# AWG_mechanics.net
KiCad netlist of a schematic drawn in Altium Designer
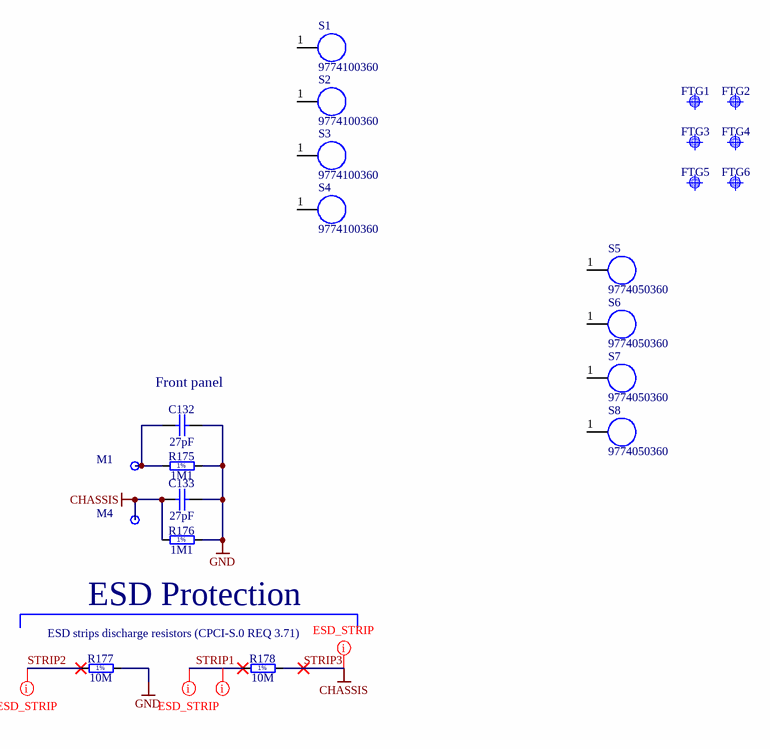
[diagram p0: AWG_mechanics.SchDoc]

(export (version "E")
  (design (tool "Eeschema 10.0.6"))
  (components
    (comp (ref "C132")
      (value "27pF")
      (footprint "CAPC1005X55N")
      (description "Non-polarised capacitor")
      (fields
        (field (name "PART NUMBER") "CC0402_27PF_50V_5%_C0G")
        (field (name "VOLTAGE") "50V")
        (field (name "AUTHOR") "CERN DEM JLC")
      )
      (libsource (lib "Capacitors") (part "Capacitor - non polarized"))
    )
    (comp (ref "C133")
      (value "27pF")
      (footprint "CAPC1005X55N")
      (description "Non-polarised capacitor")
      (fields
        (field (name "PART NUMBER") "CC0402_27PF_50V_5%_C0G")
        (field (name "VOLTAGE") "50V")
        (field (name "AUTHOR") "CERN DEM JLC")
      )
      (libsource (lib "Capacitors") (part "Capacitor - non polarized"))
    )
    (comp (ref "FTG1")
      (value "Use only in PCB")
      (footprint "FIDUCIAL_TOP_C100-200")
      (description "Fiducial Target")
      (fields (field (name "PART NUMBER") "FIDUCIAL_TARGET_C100-200") (field (name "AUTHOR") "CERN DEM JLC"))
      (libsource (lib "Eletro-mechanical") (part "Fiducial Target"))
    )
    (comp (ref "FTG2")
      (value "Use only in PCB")
      (footprint "FIDUCIAL_TOP_S100-200")
      (description "Fiducial Target")
      (fields (field (name "PART NUMBER") "FIDUCIAL_TARGET_S100-200") (field (name "AUTHOR") "CERN DEM JLC"))
      (libsource (lib "Eletro-mechanical") (part "Fiducial Target"))
    )
    (comp (ref "FTG3")
      (value "Use only in PCB")
      (footprint "FIDUCIAL_TOP_C100-200")
      (description "Fiducial Target")
      (fields (field (name "PART NUMBER") "FIDUCIAL_TARGET_C100-200") (field (name "AUTHOR") "CERN DEM JLC"))
      (libsource (lib "Eletro-mechanical") (part "Fiducial Target"))
    )
    (comp (ref "FTG4")
      (value "Use only in PCB")
      (footprint "FIDUCIAL_TOP_S100-200")
      (description "Fiducial Target")
      (fields (field (name "PART NUMBER") "FIDUCIAL_TARGET_S100-200") (field (name "AUTHOR") "CERN DEM JLC"))
      (libsource (lib "Eletro-mechanical") (part "Fiducial Target"))
    )
    (comp (ref "FTG5")
      (value "Use only in PCB")
      (footprint "FIDUCIAL_TOP_C100-200")
      (description "Fiducial Target")
      (fields (field (name "PART NUMBER") "FIDUCIAL_TARGET_C100-200") (field (name "AUTHOR") "CERN DEM JLC"))
      (libsource (lib "Eletro-mechanical") (part "Fiducial Target"))
    )
    (comp (ref "FTG6")
      (value "Use only in PCB")
      (footprint "FIDUCIAL_TOP_S100-200")
      (description "Fiducial Target")
      (fields (field (name "PART NUMBER") "FIDUCIAL_TARGET_S100-200") (field (name "AUTHOR") "CERN DEM JLC"))
      (libsource (lib "Eletro-mechanical") (part "Fiducial Target"))
    )
    (comp (ref "M1")
      (value "Plated Hole")
      (footprint "MTG300_600")
      (description "Single Terminal Socket")
      (fields (field (name "PART NUMBER") "PLATED_HOLE3.0_PAD6.0") (field (name "AUTHOR") "CERN DEM JLC"))
      (libsource (lib "Eletro-mechanical") (part "Single Terminal Socket"))
    )
    (comp (ref "M4")
      (value "Plated Hole")
      (footprint "MTG300_600")
      (description "Single Terminal Socket")
      (fields (field (name "PART NUMBER") "PLATED_HOLE3.0_PAD6.0") (field (name "AUTHOR") "CERN DEM JLC"))
      (libsource (lib "Eletro-mechanical") (part "Single Terminal Socket"))
    )
    (comp (ref "R175")
      (value "1M1")
      (footprint "RESC2012X60N")
      (description "Resistor - 1%")
      (fields
        (field (name "PART NUMBER") "R0805_1M1_1%_0.125W_100PPM")
        (field (name "POWER") "0.125W")
        (field (name "AUTHOR") "CERN DEM JLC")
      )
      (libsource (lib "Resistors") (part "Resistor - 1%"))
    )
    (comp (ref "R176")
      (value "1M1")
      (footprint "RESC2012X60N")
      (description "Resistor - 1%")
      (fields
        (field (name "PART NUMBER") "R0805_1M1_1%_0.125W_100PPM")
        (field (name "POWER") "0.125W")
        (field (name "AUTHOR") "CERN DEM JLC")
      )
      (libsource (lib "Resistors") (part "Resistor - 1%"))
    )
    (comp (ref "R177")
      (value "10M")
      (footprint "RESC2113X55N")
      (description "Resistor - 1%")
      (fields
        (field (name "PART NUMBER") "R0805_10M_1%_0.125W_100PPM_VISHAY_CRCW e3")
        (field (name "POWER") "0.125W")
        (field (name "AUTHOR") "CERN DEM BC")
      )
      (libsource (lib "Resistors") (part "Resistor - 1%"))
    )
    (comp (ref "R178")
      (value "10M")
      (footprint "RESC2113X55N")
      (description "Resistor - 1%")
      (fields
        (field (name "PART NUMBER") "R0805_10M_1%_0.125W_100PPM_VISHAY_CRCW e3")
        (field (name "POWER") "0.125W")
        (field (name "AUTHOR") "CERN DEM BC")
      )
      (libsource (lib "Resistors") (part "Resistor - 1%"))
    )
    (comp (ref "S1")
      (value "9774100360")
      (footprint "9774100360")
      (description "WA-SMSI SMD Steel Spacer with internal Thread")
      (fields (field (name "MANUFACTURER") "Wurth Elektronik") (field (name "CREATED BY") "Baojun Chen"))
      (libsource (lib "Altium_SMSI_SMT_STEEL_SPACER_M2_5_THREAD_INTERNAL_rev15a") (part "WA-SMSI,  9774100360"))
    )
    (comp (ref "S2")
      (value "9774100360")
      (footprint "9774100360")
      (description "WA-SMSI SMD Steel Spacer with internal Thread")
      (fields (field (name "MANUFACTURER") "Wurth Elektronik") (field (name "CREATED BY") "Baojun Chen"))
      (libsource (lib "Altium_SMSI_SMT_STEEL_SPACER_M2_5_THREAD_INTERNAL_rev15a") (part "WA-SMSI,  9774100360"))
    )
    (comp (ref "S3")
      (value "9774100360")
      (footprint "9774100360")
      (description "WA-SMSI SMD Steel Spacer with internal Thread")
      (fields (field (name "MANUFACTURER") "Wurth Elektronik") (field (name "CREATED BY") "Baojun Chen"))
      (libsource (lib "Altium_SMSI_SMT_STEEL_SPACER_M2_5_THREAD_INTERNAL_rev15a") (part "WA-SMSI,  9774100360"))
    )
    (comp (ref "S4")
      (value "9774100360")
      (footprint "9774100360")
      (description "WA-SMSI SMD Steel Spacer with internal Thread")
      (fields (field (name "MANUFACTURER") "Wurth Elektronik") (field (name "CREATED BY") "Baojun Chen"))
      (libsource (lib "Altium_SMSI_SMT_STEEL_SPACER_M2_5_THREAD_INTERNAL_rev15a") (part "WA-SMSI,  9774100360"))
    )
    (comp (ref "S5")
      (value "9774050360")
      (footprint "9774050360")
      (description "WA-SMSI SMD Steel Spacer with internal Thread")
      (fields (field (name "MANUFACTURER") "Wurth Elektronik") (field (name "CREATED BY") "Baojun Chen"))
      (libsource (lib "Altium_SMSI_SMT_STEEL_SPACER_M2_5_THREAD_INTERNAL_rev15a") (part "WA-SMSI,  9774050360"))
    )
    (comp (ref "S6")
      (value "9774050360")
      (footprint "9774050360")
      (description "WA-SMSI SMD Steel Spacer with internal Thread")
      (fields (field (name "MANUFACTURER") "Wurth Elektronik") (field (name "CREATED BY") "Baojun Chen"))
      (libsource (lib "Altium_SMSI_SMT_STEEL_SPACER_M2_5_THREAD_INTERNAL_rev15a") (part "WA-SMSI,  9774050360"))
    )
    (comp (ref "S7")
      (value "9774050360")
      (footprint "9774050360")
      (description "WA-SMSI SMD Steel Spacer with internal Thread")
      (fields (field (name "MANUFACTURER") "Wurth Elektronik") (field (name "CREATED BY") "Baojun Chen"))
      (libsource (lib "Altium_SMSI_SMT_STEEL_SPACER_M2_5_THREAD_INTERNAL_rev15a") (part "WA-SMSI,  9774050360"))
    )
    (comp (ref "S8")
      (value "9774050360")
      (footprint "9774050360")
      (description "WA-SMSI SMD Steel Spacer with internal Thread")
      (fields (field (name "MANUFACTURER") "Wurth Elektronik") (field (name "CREATED BY") "Baojun Chen"))
      (libsource (lib "Altium_SMSI_SMT_STEEL_SPACER_M2_5_THREAD_INTERNAL_rev15a") (part "WA-SMSI,  9774050360"))
    )
  )
  (nets
    (net (code "1") (name "/STRIP1") (class "Default")
      (node (ref "R178") (pin "1") (pinfunction "1_1") (pintype "passive+no_connect"))
    )
    (net (code "2") (name "/STRIP2") (class "Default")
      (node (ref "R177") (pin "1") (pinfunction "1_1") (pintype "passive+no_connect"))
    )
    (net (code "4") (name "CHASSIS") (class "Default")
      (node (ref "C133") (pin "1") (pinfunction "1_1") (pintype "passive"))
      (node (ref "M4") (pin "1") (pinfunction "1_1") (pintype "bidirectional"))
      (node (ref "R176") (pin "1") (pinfunction "1_1") (pintype "passive"))
      (node (ref "R178") (pin "2") (pinfunction "2_2") (pintype "passive"))
    )
    (net (code "5") (name "GND") (class "Default")
      (node (ref "C132") (pin "2") (pinfunction "2_2") (pintype "passive"))
      (node (ref "C133") (pin "2") (pinfunction "2_2") (pintype "passive"))
      (node (ref "R175") (pin "2") (pinfunction "2_2") (pintype "passive"))
      (node (ref "R176") (pin "2") (pinfunction "2_2") (pintype "passive"))
      (node (ref "R177") (pin "2") (pinfunction "2_2") (pintype "passive"))
    )
    (net (code "6") (name "Net-(C132-Pad1)") (class "Default")
      (node (ref "C132") (pin "1") (pinfunction "1_1") (pintype "passive"))
      (node (ref "M1") (pin "1") (pinfunction "1_1") (pintype "bidirectional"))
      (node (ref "R175") (pin "1") (pinfunction "1_1") (pintype "passive"))
    )
    (net (code "7") (name "unconnected-(S1-Pad1)") (class "Default")
      (node (ref "S1") (pin "1") (pinfunction "1_1") (pintype "passive"))
    )
    (net (code "8") (name "unconnected-(S2-Pad1)") (class "Default")
      (node (ref "S2") (pin "1") (pinfunction "1_1") (pintype "passive"))
    )
    (net (code "9") (name "unconnected-(S3-Pad1)") (class "Default")
      (node (ref "S3") (pin "1") (pinfunction "1_1") (pintype "passive"))
    )
    (net (code "10") (name "unconnected-(S4-Pad1)") (class "Default")
      (node (ref "S4") (pin "1") (pinfunction "1_1") (pintype "passive"))
    )
    (net (code "11") (name "unconnected-(S5-Pad1)") (class "Default")
      (node (ref "S5") (pin "1") (pinfunction "1_1") (pintype "passive"))
    )
    (net (code "12") (name "unconnected-(S6-Pad1)") (class "Default")
      (node (ref "S6") (pin "1") (pinfunction "1_1") (pintype "passive"))
    )
    (net (code "13") (name "unconnected-(S7-Pad1)") (class "Default")
      (node (ref "S7") (pin "1") (pinfunction "1_1") (pintype "passive"))
    )
    (net (code "14") (name "unconnected-(S8-Pad1)") (class "Default")
      (node (ref "S8") (pin "1") (pinfunction "1_1") (pintype "passive"))
    )
  )
)
